# pojstka.net
KiCad netlist of a schematic drawn in EAGLE
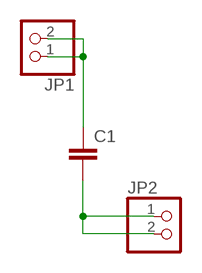
[diagram p0: schematic, sheet 1]

(export (version "E")
  (design (tool "Eeschema 10.0.6"))
  (components
    (comp (ref "C1")
      (value "C-EU225-087X268")
      (footprint "eagle-import:C225-087X268")
      (libsource (lib "eagle-import") (part "C-EU225-087X268"))
    )
    (comp (ref "JP1")
      (value "PINHD-1X2")
      (footprint "eagle-import:1X02")
      (libsource (lib "eagle-import") (part "PINHD-1X2"))
    )
    (comp (ref "JP2")
      (value "PINHD-1X2")
      (footprint "eagle-import:1X02")
      (libsource (lib "eagle-import") (part "PINHD-1X2"))
    )
  )
  (nets
    (net (code "1") (name "Net-(C1-Pad1)") (class "Default")
      (node (ref "C1") (pin "1") (pinfunction "1_1") (pintype "passive"))
      (node (ref "JP1") (pin "1") (pinfunction "1_1") (pintype "passive"))
      (node (ref "JP1") (pin "2") (pinfunction "2_2") (pintype "passive"))
    )
    (net (code "2") (name "Net-(C1-Pad2)") (class "Default")
      (node (ref "C1") (pin "2") (pinfunction "2_2") (pintype "passive"))
      (node (ref "JP2") (pin "1") (pinfunction "1_1") (pintype "passive"))
      (node (ref "JP2") (pin "2") (pinfunction "2_2") (pintype "passive"))
    )
  )
)
